# psxpwr.net
KiCad netlist of a schematic drawn in EAGLE
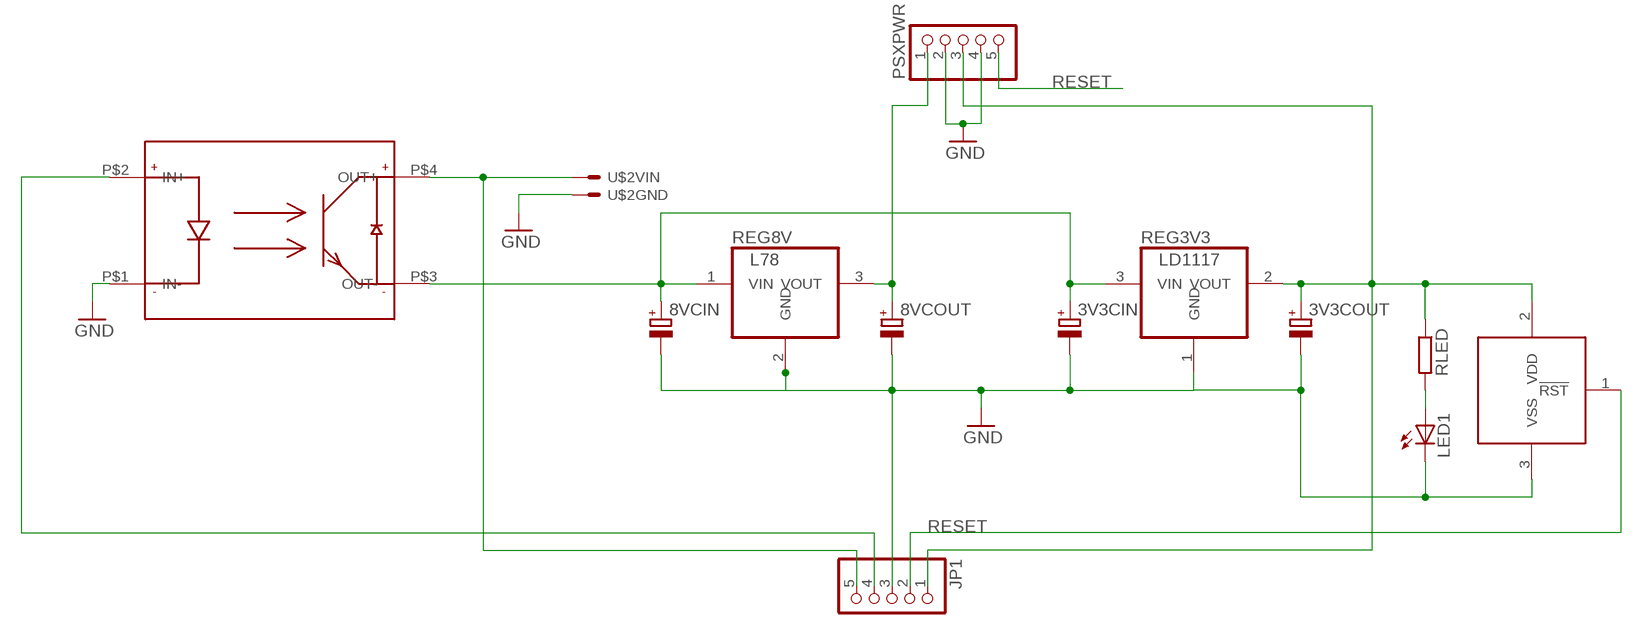
[diagram p0: schematic, sheet 1]

(export (version "E")
  (design (tool "Eeschema 10.0.6"))
  (components
    (comp (ref "3V3CIN")
      (value "CPOL-EUE2.5-6")
      (footprint "eagle-import:E2,5-6")
      (libsource (lib "eagle-import") (part "CPOL-EUE2.5-6"))
    )
    (comp (ref "3V3COUT")
      (value "CPOL-EUE2.5-6")
      (footprint "eagle-import:E2,5-6")
      (libsource (lib "eagle-import") (part "CPOL-EUE2.5-6"))
    )
    (comp (ref "8VCIN")
      (value "CPOL-EUE2.5-6")
      (footprint "eagle-import:E2,5-6")
      (libsource (lib "eagle-import") (part "CPOL-EUE2.5-6"))
    )
    (comp (ref "8VCOUT")
      (value "CPOL-EUE2.5-6")
      (footprint "eagle-import:E2,5-6")
      (libsource (lib "eagle-import") (part "CPOL-EUE2.5-6"))
    )
    (comp (ref "JP1")
      (value "PINHD-1X5")
      (footprint "eagle-import:1X05")
      (libsource (lib "eagle-import") (part "PINHD-1X5"))
    )
    (comp (ref "LED1")
      (value "LED3MM")
      (footprint "eagle-import:LED3MM")
      (libsource (lib "eagle-import") (part "LED3MM"))
    )
    (comp (ref "PSXPWR")
      (value "PINHD-1X5")
      (footprint "eagle-import:1X05")
      (libsource (lib "eagle-import") (part "PINHD-1X5"))
    )
    (comp (ref "REG3V3")
      (value "LD1117")
      (footprint "eagle-import:TO-220-HEATSINK")
      (libsource (lib "eagle-import") (part "LD1117"))
    )
    (comp (ref "REG8V")
      (value "L78")
      (footprint "eagle-import:TO-220-HEATSINK")
      (libsource (lib "eagle-import") (part "L78"))
    )
    (comp (ref "RESET")
      (value "MCP100V3")
      (footprint "eagle-import:TO92-EBC-OVAL")
      (libsource (lib "eagle-import") (part "MCP100V3"))
    )
    (comp (ref "RLED")
      (value "R-EU_0207/2V")
      (footprint "eagle-import:0207_2V")
      (libsource (lib "eagle-import") (part "R-EU_0207/2V"))
    )
    (comp (ref "U$1")
      (value "KF060XD")
      (footprint "eagle-import:KF060XD")
      (libsource (lib "eagle-import") (part "KF060XD"))
    )
    (comp (ref "U$2")
      (value "PWR")
      (footprint "eagle-import:PWR")
      (libsource (lib "eagle-import") (part "PWR"))
    )
  )
  (nets
    (net (code "1") (name "/RESET") (class "Default")
      (node (ref "JP1") (pin "2") (pinfunction "2_2") (pintype "passive"))
      (node (ref "PSXPWR") (pin "5") (pinfunction "5_5") (pintype "passive"))
      (node (ref "RESET") (pin "1") (pinfunction "~{RST}_1") (pintype "bidirectional"))
    )
    (net (code "2") (name "GND") (class "Default")
      (node (ref "3V3CIN") (pin "-") (pinfunction "-_-") (pintype "passive"))
      (node (ref "3V3COUT") (pin "-") (pinfunction "-_-") (pintype "passive"))
      (node (ref "8VCIN") (pin "-") (pinfunction "-_-") (pintype "passive"))
      (node (ref "8VCOUT") (pin "-") (pinfunction "-_-") (pintype "passive"))
      (node (ref "JP1") (pin "3") (pinfunction "3_3") (pintype "passive"))
      (node (ref "LED1") (pin "K") (pinfunction "C_K") (pintype "passive"))
      (node (ref "PSXPWR") (pin "2") (pinfunction "2_2") (pintype "passive"))
      (node (ref "PSXPWR") (pin "4") (pinfunction "4_4") (pintype "passive"))
      (node (ref "REG3V3") (pin "1") (pinfunction "GND_1") (pintype "power_in"))
      (node (ref "REG8V") (pin "2") (pinfunction "GND_2") (pintype "power_in"))
      (node (ref "RESET") (pin "3") (pinfunction "VSS_3") (pintype "bidirectional"))
      (node (ref "U$1") (pin "P$1") (pinfunction "IN-_P$1") (pintype "bidirectional"))
      (node (ref "U$2") (pin "P$1") (pinfunction "S_P$1") (pintype "passive"))
    )
    (net (code "3") (name "Net-(LED1-PadA)") (class "Default")
      (node (ref "LED1") (pin "A") (pinfunction "A_A") (pintype "passive"))
      (node (ref "RLED") (pin "2") (pinfunction "2_2") (pintype "passive"))
    )
    (net (code "4") (name "Net-(REG3V3-VIN)") (class "Default")
      (node (ref "3V3CIN") (pin "+") (pinfunction "+_+") (pintype "passive"))
      (node (ref "8VCIN") (pin "+") (pinfunction "+_+") (pintype "passive"))
      (node (ref "REG3V3") (pin "3") (pinfunction "VIN_3") (pintype "input"))
      (node (ref "REG8V") (pin "1") (pinfunction "VIN_1") (pintype "input"))
      (node (ref "U$1") (pin "P$3") (pinfunction "OUT-_P$3") (pintype "bidirectional"))
    )
    (net (code "5") (name "Net-(REG3V3-VOUT)") (class "Default")
      (node (ref "3V3COUT") (pin "+") (pinfunction "+_+") (pintype "passive"))
      (node (ref "JP1") (pin "1") (pinfunction "1_1") (pintype "passive"))
      (node (ref "PSXPWR") (pin "3") (pinfunction "3_3") (pintype "passive"))
      (node (ref "REG3V3") (pin "2") (pinfunction "VOUT_2") (pintype "output"))
      (node (ref "RESET") (pin "2") (pinfunction "VDD_2") (pintype "bidirectional"))
      (node (ref "RLED") (pin "1") (pinfunction "1_1") (pintype "passive"))
    )
    (net (code "6") (name "Net-(REG8V-VOUT)") (class "Default")
      (node (ref "8VCOUT") (pin "+") (pinfunction "+_+") (pintype "passive"))
      (node (ref "PSXPWR") (pin "1") (pinfunction "1_1") (pintype "passive"))
      (node (ref "REG8V") (pin "3") (pinfunction "VOUT_3") (pintype "output"))
    )
    (net (code "7") (name "Net-(U$1-IN+)") (class "Default")
      (node (ref "JP1") (pin "4") (pinfunction "4_4") (pintype "passive"))
      (node (ref "U$1") (pin "P$2") (pinfunction "IN+_P$2") (pintype "bidirectional"))
    )
    (net (code "8") (name "Net-(U$1-OUT+)") (class "Default")
      (node (ref "JP1") (pin "5") (pinfunction "5_5") (pintype "passive"))
      (node (ref "U$1") (pin "P$4") (pinfunction "OUT+_P$4") (pintype "bidirectional"))
      (node (ref "U$2") (pin "P$2") (pinfunction "S_P$2") (pintype "passive"))
    )
  )
)
